# stm32_bracelet.net
KiCad netlist of a schematic drawn in EasyEDA Pro
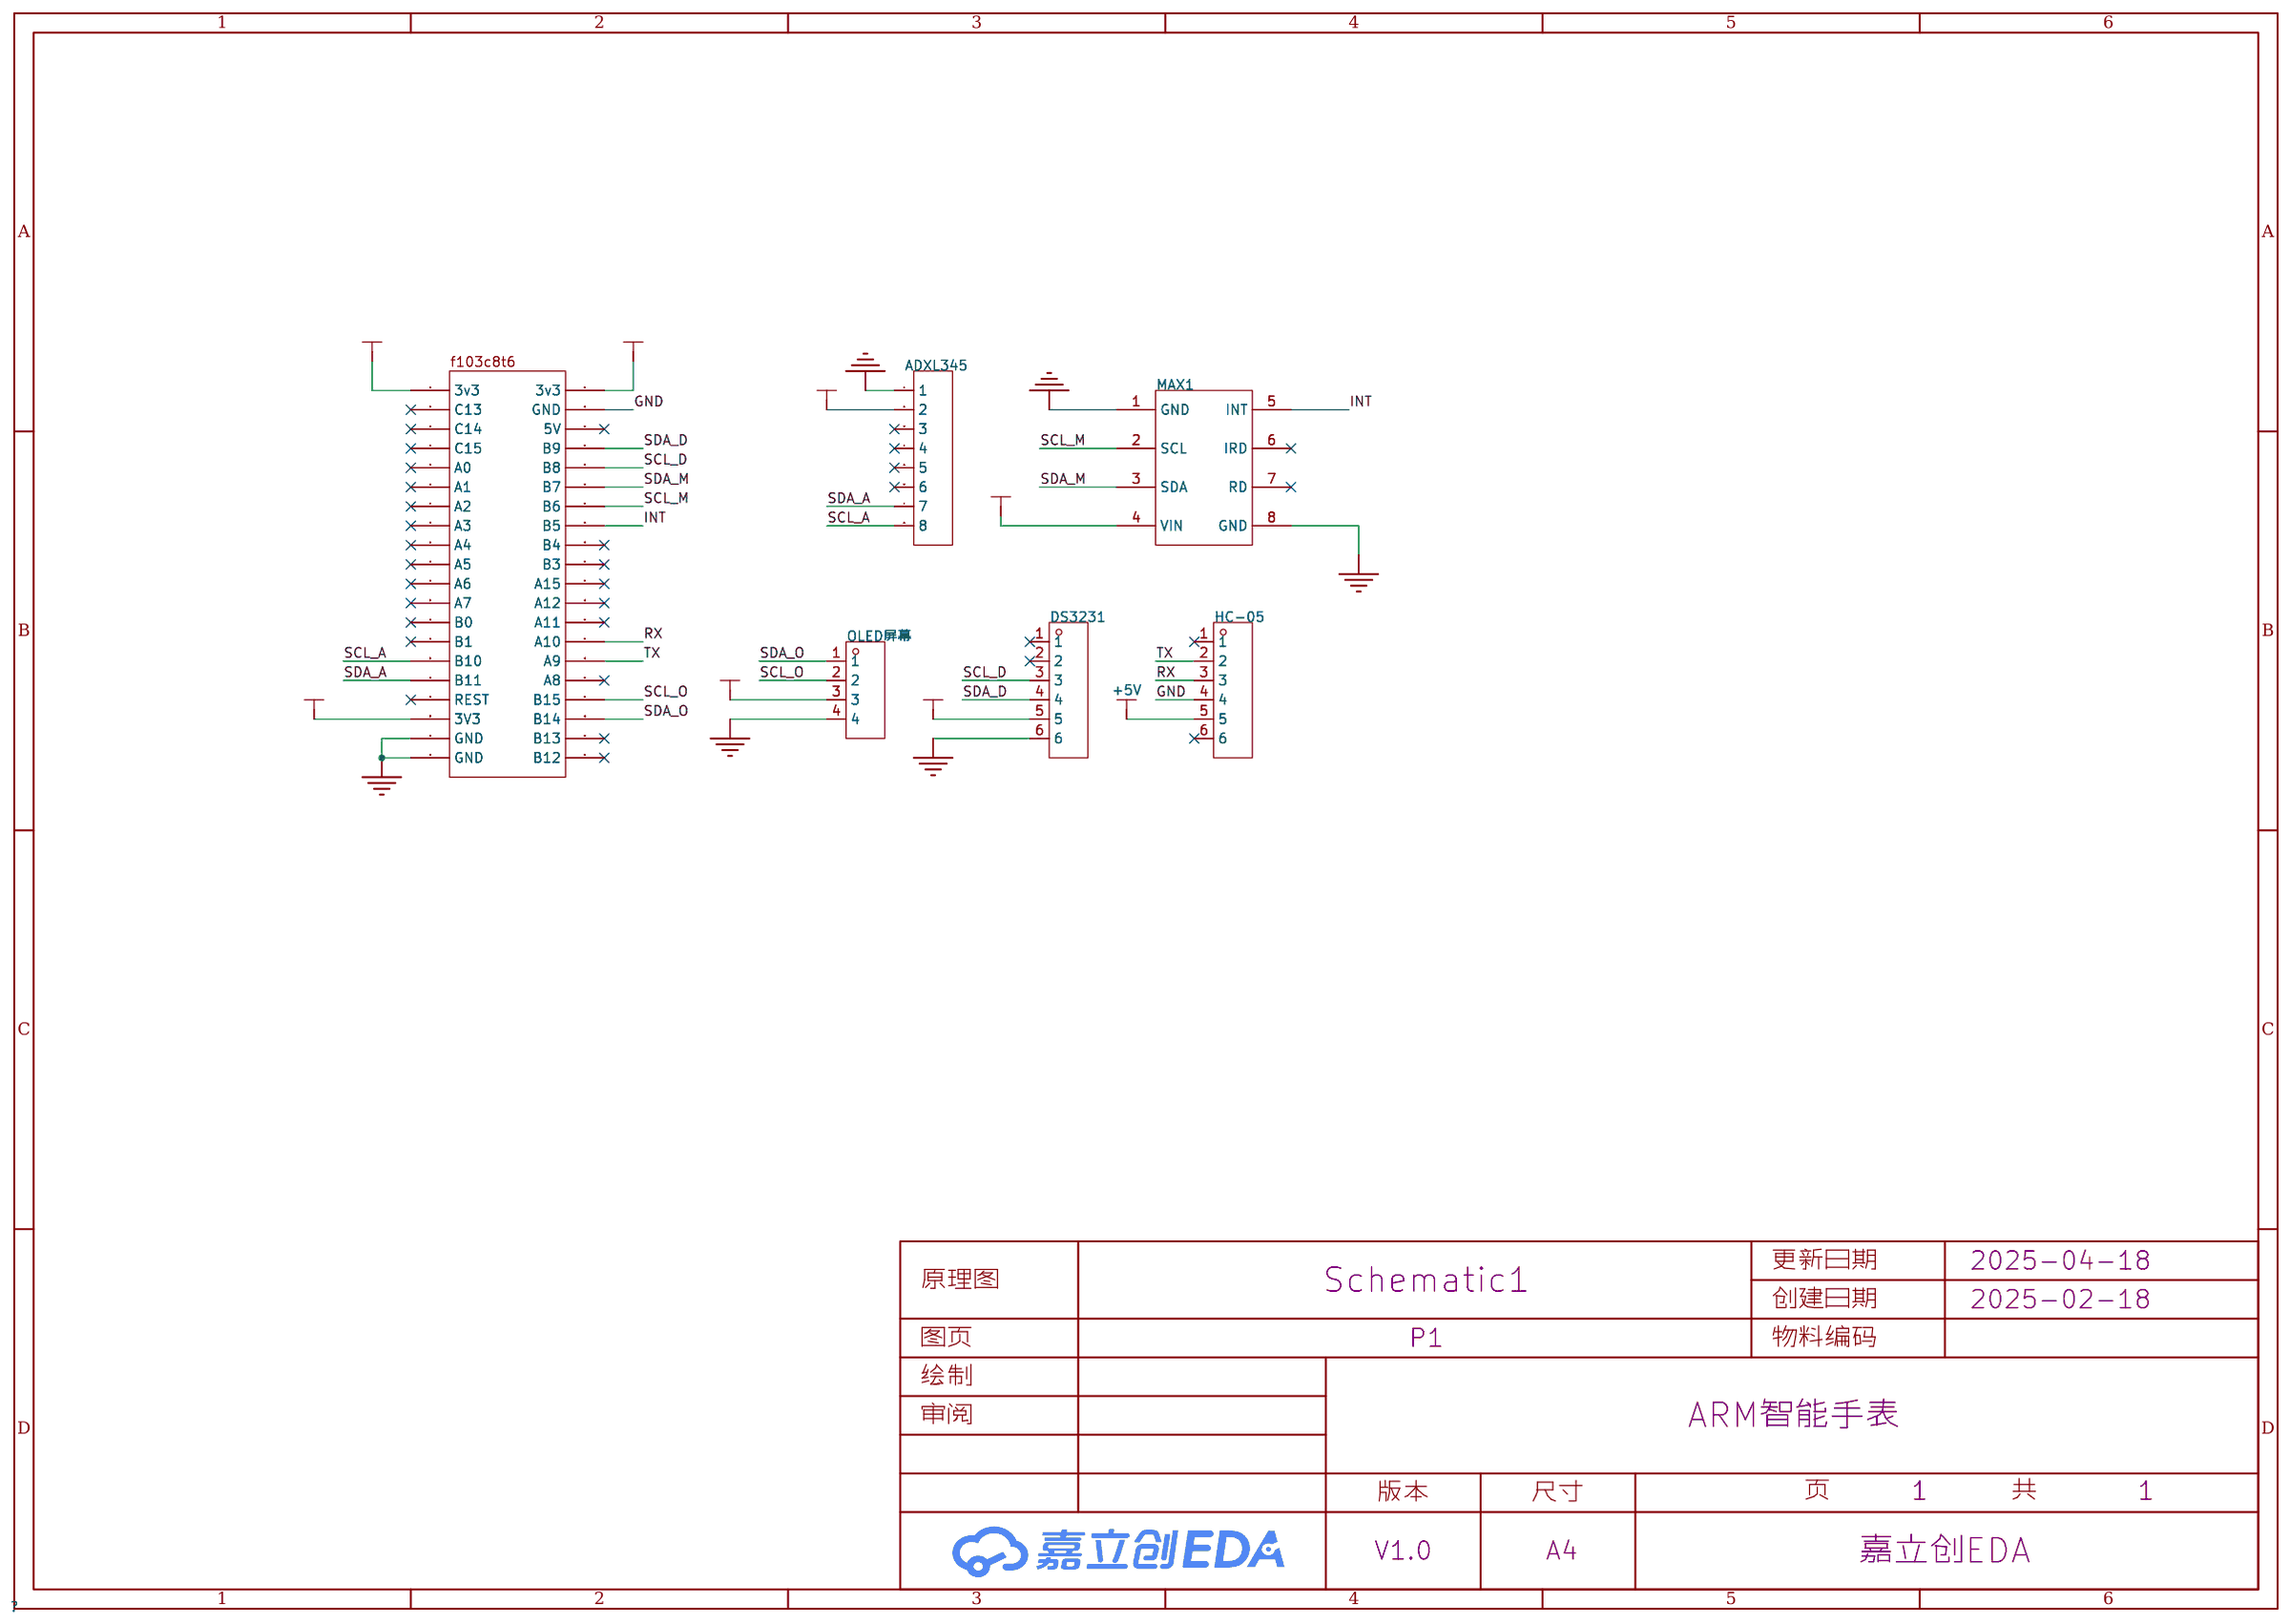
[diagram p0: schematic sheet]

(export (version "E")
  (design (tool "Eeschema 10.0.6"))
  (components
    (comp (ref "ADXL1")
      (value "ADXL345")
      (footprint "easyedapro:HDR-TH_8P-P2.54-V-F-1")
      (libsource (lib "easyedapro") (part "Header-Female-2.54_1x8"))
    )
    (comp (ref "DS1")
      (value "DS3231")
      (footprint "easyedapro:HDR-TH_6P-P2.54-V-F")
      (libsource (lib "easyedapro") (part "Header-Female-2.54_1x6"))
    )
    (comp (ref "HC1")
      (value "HC-05")
      (footprint "easyedapro:HDR-TH_6P-P2.54-V-F")
      (libsource (lib "easyedapro") (part "Header-Female-2.54_1x6"))
    )
    (comp (ref "MAX1")
      (value "~")
      (footprint "easyedapro:MAX30102")
      (libsource (lib "easyedapro") (part "MAX30102"))
    )
    (comp (ref "U1")
      (value "~")
      (footprint "easyedapro:stm32f103c8t6最小系统板")
      (libsource (lib "easyedapro") (part "stm32f103c8t6最小系统板"))
    )
    (comp (ref "U2")
      (value "OLED屏幕")
      (footprint "easyedapro:HDR-TH_4P-P2.54-V-F")
      (libsource (lib "easyedapro") (part "2.54-1*4P母"))
    )
  )
  (nets
    (net (code "1") (name "+5V") (class "Default")
      (node (ref "HC1") (pin "5") (pinfunction "5_5") (pintype "unspecified"))
    )
    (net (code "2") (name "/INT") (class "Default")
      (node (ref "MAX1") (pin "5") (pinfunction "INT_5") (pintype "input"))
      (node (ref "U1") (pin "28") (pinfunction "B5_28") (pintype "input"))
    )
    (net (code "3") (name "/RX") (class "Default")
      (node (ref "HC1") (pin "3") (pinfunction "3_3") (pintype "unspecified"))
      (node (ref "U1") (pin "34") (pinfunction "A10_34") (pintype "input"))
    )
    (net (code "4") (name "/SCL_A") (class "Default")
      (node (ref "ADXL1") (pin "8") (pinfunction "8_8") (pintype "input"))
      (node (ref "U1") (pin "15") (pinfunction "B10_15") (pintype "input"))
    )
    (net (code "5") (name "/SCL_D") (class "Default")
      (node (ref "DS1") (pin "3") (pinfunction "3_3") (pintype "unspecified"))
      (node (ref "U1") (pin "25") (pinfunction "B8_25") (pintype "input"))
    )
    (net (code "6") (name "/SCL_M") (class "Default")
      (node (ref "MAX1") (pin "2") (pinfunction "SCL_2") (pintype "input"))
      (node (ref "U1") (pin "27") (pinfunction "B6_27") (pintype "input"))
    )
    (net (code "7") (name "/SCL_O") (class "Default")
      (node (ref "U1") (pin "37") (pinfunction "B15_37") (pintype "input"))
      (node (ref "U2") (pin "2") (pinfunction "2_2") (pintype "unspecified"))
    )
    (net (code "8") (name "/SDA_A") (class "Default")
      (node (ref "ADXL1") (pin "7") (pinfunction "7_7") (pintype "input"))
      (node (ref "U1") (pin "16") (pinfunction "B11_16") (pintype "input"))
    )
    (net (code "9") (name "/SDA_D") (class "Default")
      (node (ref "DS1") (pin "4") (pinfunction "4_4") (pintype "unspecified"))
      (node (ref "U1") (pin "24") (pinfunction "B9_24") (pintype "input"))
    )
    (net (code "10") (name "/SDA_M") (class "Default")
      (node (ref "MAX1") (pin "3") (pinfunction "SDA_3") (pintype "input"))
      (node (ref "U1") (pin "26") (pinfunction "B7_26") (pintype "input"))
    )
    (net (code "11") (name "/SDA_O") (class "Default")
      (node (ref "U1") (pin "38") (pinfunction "B14_38") (pintype "input"))
      (node (ref "U2") (pin "1") (pinfunction "1_1") (pintype "unspecified"))
    )
    (net (code "12") (name "/TX") (class "Default")
      (node (ref "HC1") (pin "2") (pinfunction "2_2") (pintype "unspecified"))
      (node (ref "U1") (pin "35") (pinfunction "A9_35") (pintype "input"))
    )
    (net (code "13") (name "3V3") (class "Default")
      (node (ref "ADXL1") (pin "2") (pinfunction "2_2") (pintype "input"))
      (node (ref "DS1") (pin "5") (pinfunction "5_5") (pintype "unspecified"))
      (node (ref "MAX1") (pin "4") (pinfunction "VIN_4") (pintype "input"))
      (node (ref "U1") (pin "1") (pinfunction "3v3_1") (pintype "input"))
      (node (ref "U1") (pin "18") (pinfunction "3V3_18") (pintype "input"))
      (node (ref "U1") (pin "21") (pinfunction "3v3_21") (pintype "input"))
      (node (ref "U2") (pin "3") (pinfunction "3_3") (pintype "unspecified"))
    )
    (net (code "14") (name "GND") (class "Default")
      (node (ref "ADXL1") (pin "1") (pinfunction "1_1") (pintype "input"))
      (node (ref "DS1") (pin "6") (pinfunction "6_6") (pintype "unspecified"))
      (node (ref "HC1") (pin "4") (pinfunction "4_4") (pintype "unspecified"))
      (node (ref "MAX1") (pin "1") (pinfunction "GND_1") (pintype "input"))
      (node (ref "MAX1") (pin "8") (pinfunction "GND_8") (pintype "input"))
      (node (ref "U1") (pin "19") (pinfunction "GND_19") (pintype "input"))
      (node (ref "U1") (pin "20") (pinfunction "GND_20") (pintype "input"))
      (node (ref "U1") (pin "22") (pinfunction "GND_22") (pintype "input"))
      (node (ref "U2") (pin "4") (pinfunction "4_4") (pintype "unspecified"))
    )
    (net (code "15") (name "unconnected-(ADXL1-Pad3)") (class "Default")
      (node (ref "ADXL1") (pin "3") (pinfunction "3_3") (pintype "input+no_connect"))
    )
    (net (code "16") (name "unconnected-(ADXL1-Pad4)") (class "Default")
      (node (ref "ADXL1") (pin "4") (pinfunction "4_4") (pintype "input+no_connect"))
    )
    (net (code "17") (name "unconnected-(ADXL1-Pad5)") (class "Default")
      (node (ref "ADXL1") (pin "5") (pinfunction "5_5") (pintype "input+no_connect"))
    )
    (net (code "18") (name "unconnected-(ADXL1-Pad6)") (class "Default")
      (node (ref "ADXL1") (pin "6") (pinfunction "6_6") (pintype "input+no_connect"))
    )
    (net (code "19") (name "unconnected-(DS1-Pad1)") (class "Default")
      (node (ref "DS1") (pin "1") (pinfunction "1_1") (pintype "unspecified+no_connect"))
    )
    (net (code "20") (name "unconnected-(DS1-Pad2)") (class "Default")
      (node (ref "DS1") (pin "2") (pinfunction "2_2") (pintype "unspecified+no_connect"))
    )
    (net (code "21") (name "unconnected-(HC1-Pad1)") (class "Default")
      (node (ref "HC1") (pin "1") (pinfunction "1_1") (pintype "unspecified+no_connect"))
    )
    (net (code "22") (name "unconnected-(HC1-Pad6)") (class "Default")
      (node (ref "HC1") (pin "6") (pinfunction "6_6") (pintype "unspecified+no_connect"))
    )
    (net (code "23") (name "unconnected-(MAX1-IRD-Pad6)") (class "Default")
      (node (ref "MAX1") (pin "6") (pinfunction "IRD_6") (pintype "input+no_connect"))
    )
    (net (code "24") (name "unconnected-(MAX1-RD-Pad7)") (class "Default")
      (node (ref "MAX1") (pin "7") (pinfunction "RD_7") (pintype "input+no_connect"))
    )
    (net (code "25") (name "unconnected-(U1-5V-Pad23)") (class "Default")
      (node (ref "U1") (pin "23") (pinfunction "5V_23") (pintype "input+no_connect"))
    )
    (net (code "26") (name "unconnected-(U1-A0-Pad5)") (class "Default")
      (node (ref "U1") (pin "5") (pinfunction "A0_5") (pintype "input+no_connect"))
    )
    (net (code "27") (name "unconnected-(U1-A1-Pad6)") (class "Default")
      (node (ref "U1") (pin "6") (pinfunction "A1_6") (pintype "input+no_connect"))
    )
    (net (code "28") (name "unconnected-(U1-A2-Pad7)") (class "Default")
      (node (ref "U1") (pin "7") (pinfunction "A2_7") (pintype "input+no_connect"))
    )
    (net (code "29") (name "unconnected-(U1-A3-Pad8)") (class "Default")
      (node (ref "U1") (pin "8") (pinfunction "A3_8") (pintype "input+no_connect"))
    )
    (net (code "30") (name "unconnected-(U1-A4-Pad9)") (class "Default")
      (node (ref "U1") (pin "9") (pinfunction "A4_9") (pintype "input+no_connect"))
    )
    (net (code "31") (name "unconnected-(U1-A5-Pad10)") (class "Default")
      (node (ref "U1") (pin "10") (pinfunction "A5_10") (pintype "input+no_connect"))
    )
    (net (code "32") (name "unconnected-(U1-A6-Pad11)") (class "Default")
      (node (ref "U1") (pin "11") (pinfunction "A6_11") (pintype "input+no_connect"))
    )
    (net (code "33") (name "unconnected-(U1-A7-Pad12)") (class "Default")
      (node (ref "U1") (pin "12") (pinfunction "A7_12") (pintype "input+no_connect"))
    )
    (net (code "34") (name "unconnected-(U1-A8-Pad36)") (class "Default")
      (node (ref "U1") (pin "36") (pinfunction "A8_36") (pintype "input+no_connect"))
    )
    (net (code "35") (name "unconnected-(U1-A11-Pad33)") (class "Default")
      (node (ref "U1") (pin "33") (pinfunction "A11_33") (pintype "input+no_connect"))
    )
    (net (code "36") (name "unconnected-(U1-A12-Pad32)") (class "Default")
      (node (ref "U1") (pin "32") (pinfunction "A12_32") (pintype "input+no_connect"))
    )
    (net (code "37") (name "unconnected-(U1-A15-Pad31)") (class "Default")
      (node (ref "U1") (pin "31") (pinfunction "A15_31") (pintype "input+no_connect"))
    )
    (net (code "38") (name "unconnected-(U1-B0-Pad13)") (class "Default")
      (node (ref "U1") (pin "13") (pinfunction "B0_13") (pintype "input+no_connect"))
    )
    (net (code "39") (name "unconnected-(U1-B1-Pad14)") (class "Default")
      (node (ref "U1") (pin "14") (pinfunction "B1_14") (pintype "input+no_connect"))
    )
    (net (code "40") (name "unconnected-(U1-B3-Pad30)") (class "Default")
      (node (ref "U1") (pin "30") (pinfunction "B3_30") (pintype "input+no_connect"))
    )
    (net (code "41") (name "unconnected-(U1-B4-Pad29)") (class "Default")
      (node (ref "U1") (pin "29") (pinfunction "B4_29") (pintype "input+no_connect"))
    )
    (net (code "42") (name "unconnected-(U1-B12-Pad40)") (class "Default")
      (node (ref "U1") (pin "40") (pinfunction "B12_40") (pintype "input+no_connect"))
    )
    (net (code "43") (name "unconnected-(U1-B13-Pad39)") (class "Default")
      (node (ref "U1") (pin "39") (pinfunction "B13_39") (pintype "input+no_connect"))
    )
    (net (code "44") (name "unconnected-(U1-C13-Pad2)") (class "Default")
      (node (ref "U1") (pin "2") (pinfunction "C13_2") (pintype "input+no_connect"))
    )
    (net (code "45") (name "unconnected-(U1-C14-Pad3)") (class "Default")
      (node (ref "U1") (pin "3") (pinfunction "C14_3") (pintype "input+no_connect"))
    )
    (net (code "46") (name "unconnected-(U1-C15-Pad4)") (class "Default")
      (node (ref "U1") (pin "4") (pinfunction "C15_4") (pintype "input+no_connect"))
    )
    (net (code "47") (name "unconnected-(U1-REST-Pad17)") (class "Default")
      (node (ref "U1") (pin "17") (pinfunction "REST_17") (pintype "input+no_connect"))
    )
  )
)
